# ece411-t4-tx-hand-controlled-robot.net
KiCad netlist of a schematic drawn in EAGLE
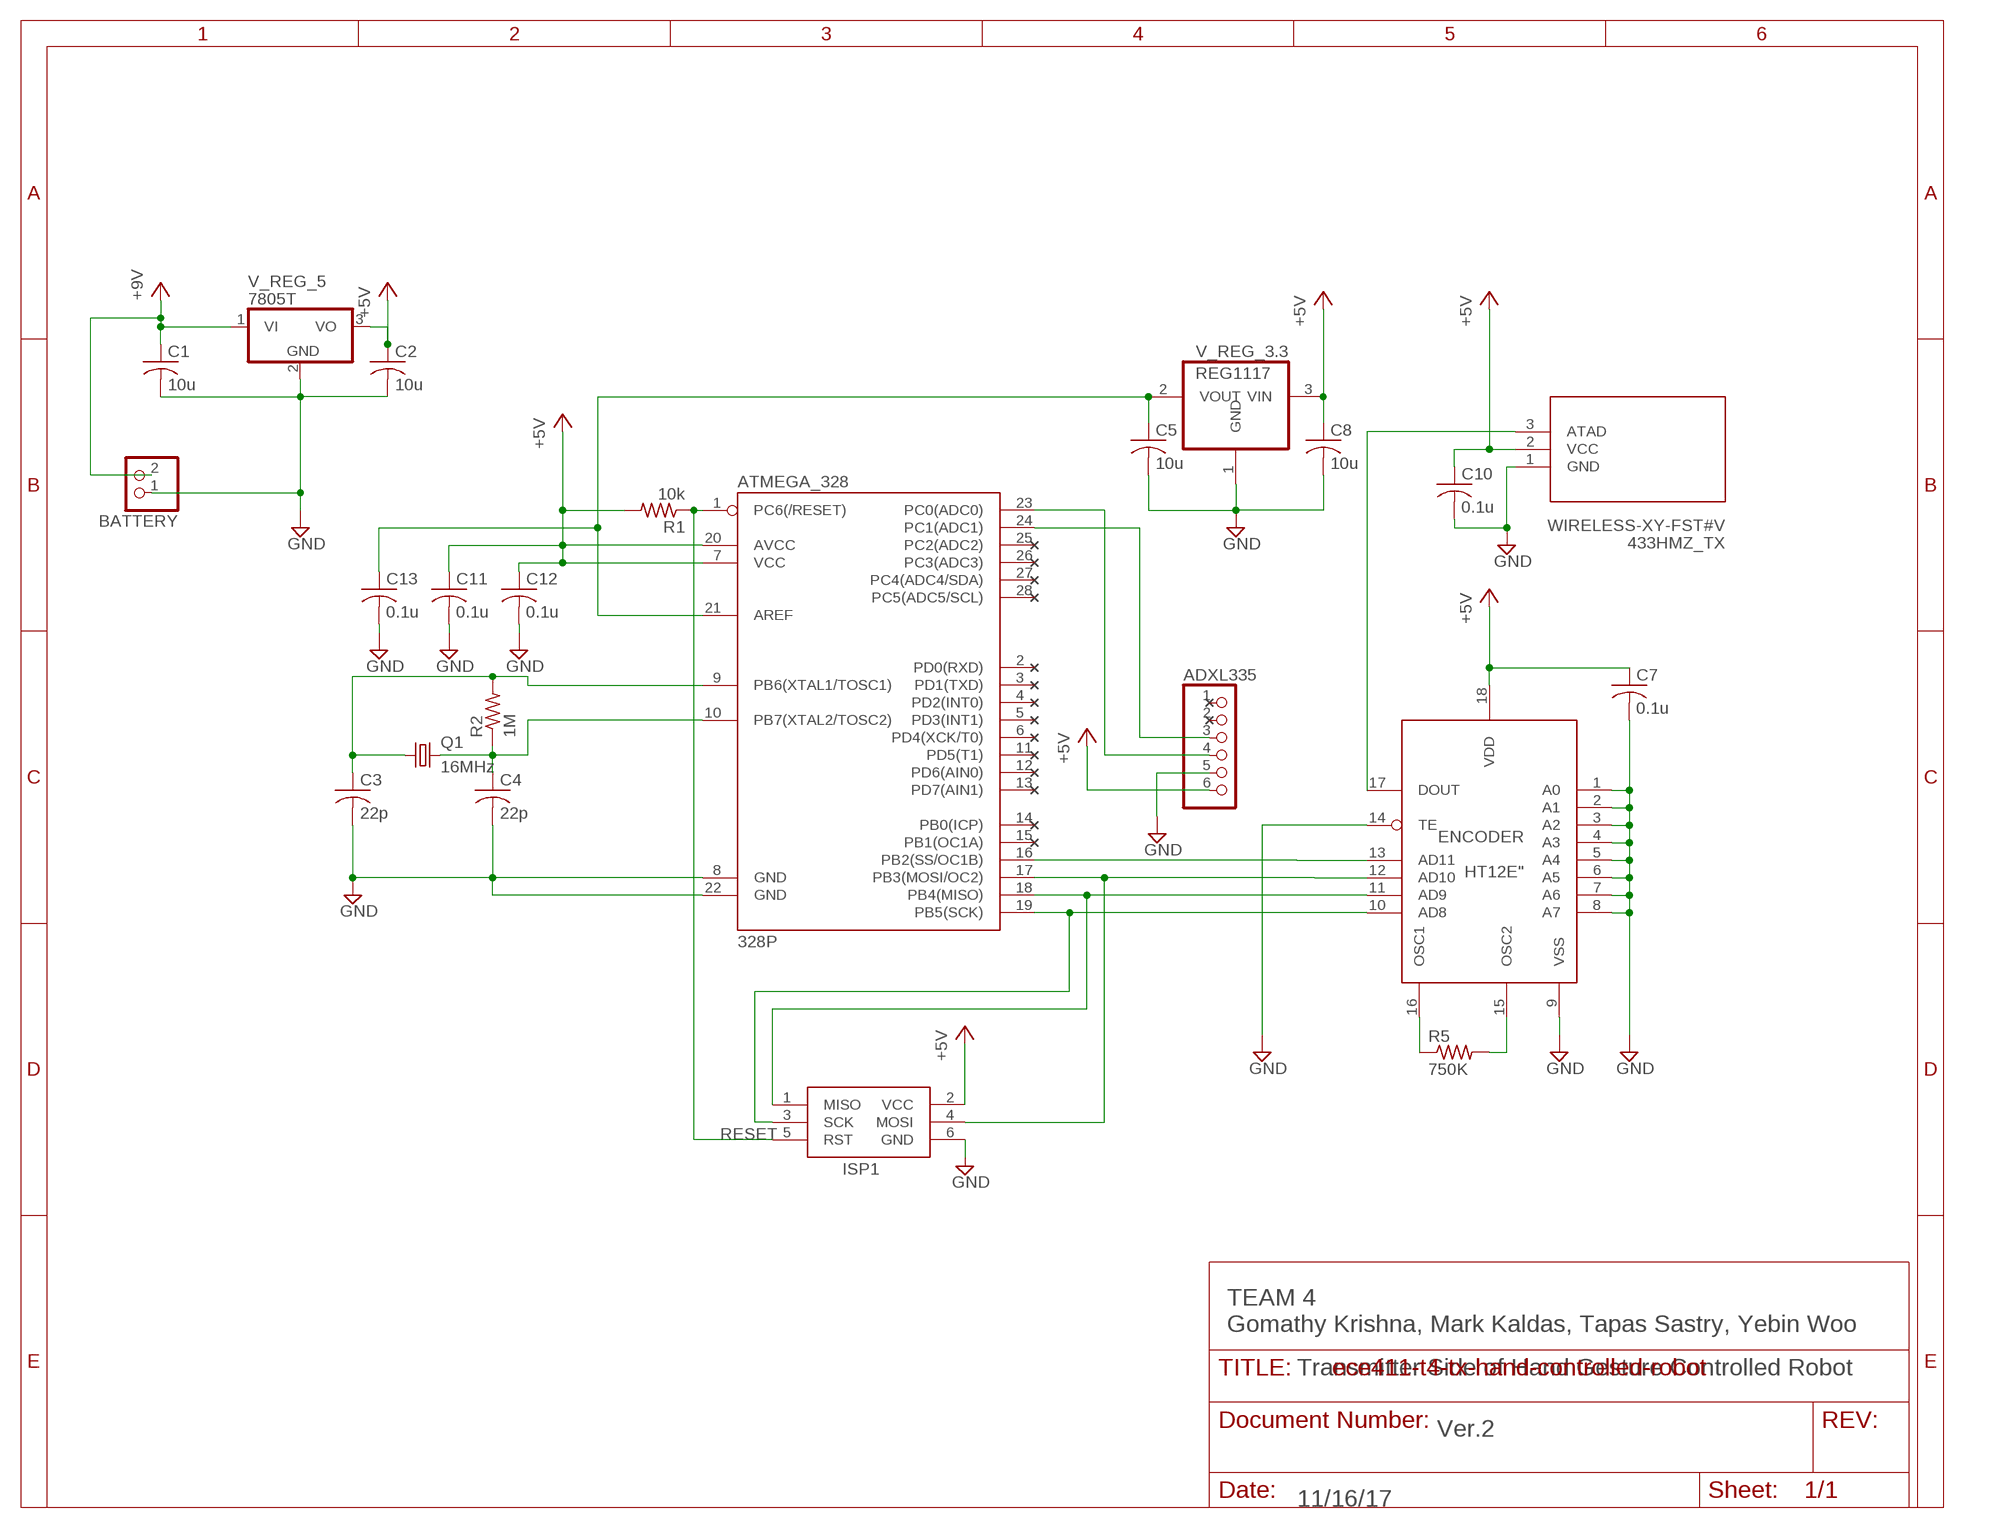
[diagram p0: schematic, sheet 1]

(export (version "E")
  (design (tool "Eeschema 10.0.6"))
  (components
    (comp (ref "433HMZ_TX")
      (value "WIRELESS-XY-FST#V")
      (footprint "eagle-import:WIRELESS-XY-FST#V")
      (libsource (lib "eagle-import") (part "WIRELESS-XY-FST#V"))
    )
    (comp (ref "ADXL335")
      (value "PINHD-1X6")
      (footprint "eagle-import:1X06")
      (libsource (lib "eagle-import") (part "PINHD-1X6"))
    )
    (comp (ref "ATMEGA_328")
      (value "328P")
      (footprint "eagle-import:DIP28")
      (libsource (lib "eagle-import") (part "ATMEGA328P_PDIP"))
    )
    (comp (ref "BATTERY")
      (value "PINHD-1X2")
      (footprint "eagle-import:1X02")
      (libsource (lib "eagle-import") (part "PINHD-1X2"))
    )
    (comp (ref "C1")
      (value "10u")
      (footprint "eagle-import:C0805")
      (libsource (lib "eagle-import") (part "C-USC0805"))
    )
    (comp (ref "C2")
      (value "10u")
      (footprint "eagle-import:C0805")
      (libsource (lib "eagle-import") (part "C-USC0805"))
    )
    (comp (ref "C3")
      (value "22p")
      (footprint "eagle-import:C0805")
      (libsource (lib "eagle-import") (part "C-USC0805"))
    )
    (comp (ref "C4")
      (value "22p")
      (footprint "eagle-import:C0805")
      (libsource (lib "eagle-import") (part "C-USC0805"))
    )
    (comp (ref "C5")
      (value "10u")
      (footprint "eagle-import:C0805")
      (libsource (lib "eagle-import") (part "C-USC0805"))
    )
    (comp (ref "C7")
      (value "0.1u")
      (footprint "eagle-import:C0805")
      (libsource (lib "eagle-import") (part "C-USC0805"))
    )
    (comp (ref "C8")
      (value "10u")
      (footprint "eagle-import:C0805")
      (libsource (lib "eagle-import") (part "C-USC0805"))
    )
    (comp (ref "C10")
      (value "0.1u")
      (footprint "eagle-import:C0805")
      (libsource (lib "eagle-import") (part "C-USC0805"))
    )
    (comp (ref "C11")
      (value "0.1u")
      (footprint "eagle-import:C0805")
      (libsource (lib "eagle-import") (part "C-USC0805"))
    )
    (comp (ref "C12")
      (value "0.1u")
      (footprint "eagle-import:C0805")
      (libsource (lib "eagle-import") (part "C-USC0805"))
    )
    (comp (ref "C13")
      (value "0.1u")
      (footprint "eagle-import:C0805")
      (libsource (lib "eagle-import") (part "C-USC0805"))
    )
    (comp (ref "ENCODER")
      (value "HT12E\"")
      (footprint "eagle-import:18-DIP-A")
      (libsource (lib "eagle-import") (part "HT12E{dblquote}"))
    )
    (comp (ref "ISP1")
      (value "AVRISP-6")
      (footprint "eagle-import:AVRISP")
      (libsource (lib "eagle-import") (part "AVRISP-6"))
    )
    (comp (ref "Q1")
      (value "16MHz")
      (footprint "eagle-import:HC49_S")
      (libsource (lib "eagle-import") (part "CRYTALHC49S"))
    )
    (comp (ref "R1")
      (value "10k")
      (footprint "eagle-import:R0805")
      (libsource (lib "eagle-import") (part "R-US_R0805"))
    )
    (comp (ref "R2")
      (value "1M")
      (footprint "eagle-import:R0805")
      (libsource (lib "eagle-import") (part "R-US_R0805"))
    )
    (comp (ref "R5")
      (value "750K")
      (footprint "eagle-import:R0805")
      (libsource (lib "eagle-import") (part "R-US_R0805"))
    )
    (comp (ref "V_REG_3.3")
      (value "REG1117")
      (footprint "eagle-import:SOT223")
      (libsource (lib "eagle-import") (part "REG1117"))
    )
    (comp (ref "V_REG_5")
      (value "7805T")
      (footprint "eagle-import:TO220H")
      (libsource (lib "eagle-import") (part "78T05"))
    )
  )
  (nets
    (net (code "1") (name "+5V") (class "Default")
      (node (ref "433HMZ_TX") (pin "2") (pinfunction "VCC_2") (pintype "power_in"))
      (node (ref "ADXL335") (pin "6") (pinfunction "6_6") (pintype "passive"))
      (node (ref "ATMEGA_328") (pin "20") (pinfunction "AVCC_20") (pintype "bidirectional"))
      (node (ref "ATMEGA_328") (pin "7") (pinfunction "VCC_7") (pintype "bidirectional"))
      (node (ref "C10") (pin "1") (pinfunction "1_1") (pintype "passive"))
      (node (ref "C11") (pin "1") (pinfunction "1_1") (pintype "passive"))
      (node (ref "C12") (pin "1") (pinfunction "1_1") (pintype "passive"))
      (node (ref "C2") (pin "1") (pinfunction "1_1") (pintype "passive"))
      (node (ref "C7") (pin "1") (pinfunction "1_1") (pintype "passive"))
      (node (ref "C8") (pin "1") (pinfunction "1_1") (pintype "passive"))
      (node (ref "ENCODER") (pin "18") (pinfunction "VDD_18") (pintype "power_in"))
      (node (ref "ISP1") (pin "2") (pinfunction "VCC_2") (pintype "power_in"))
      (node (ref "R1") (pin "2") (pinfunction "2_2") (pintype "passive"))
      (node (ref "V_REG_3.3") (pin "3") (pinfunction "VIN_3") (pintype "input"))
      (node (ref "V_REG_5") (pin "3") (pinfunction "VO_3") (pintype "passive"))
    )
    (net (code "2") (name "+9V") (class "Default")
      (node (ref "BATTERY") (pin "2") (pinfunction "2_2") (pintype "passive"))
      (node (ref "C1") (pin "1") (pinfunction "1_1") (pintype "passive"))
      (node (ref "V_REG_5") (pin "1") (pinfunction "VI_1") (pintype "input"))
    )
    (net (code "3") (name "/RESET") (class "Default")
      (node (ref "ATMEGA_328") (pin "1") (pinfunction "PC6(/RESET)_1") (pintype "bidirectional"))
      (node (ref "ISP1") (pin "5") (pinfunction "RST_5") (pintype "output"))
      (node (ref "R1") (pin "1") (pinfunction "1_1") (pintype "passive"))
    )
    (net (code "4") (name "GND") (class "Default")
      (node (ref "433HMZ_TX") (pin "1") (pinfunction "GND_1") (pintype "power_in"))
      (node (ref "ADXL335") (pin "5") (pinfunction "5_5") (pintype "passive"))
      (node (ref "ATMEGA_328") (pin "22") (pinfunction "GND_22") (pintype "bidirectional"))
      (node (ref "ATMEGA_328") (pin "8") (pinfunction "GND_8") (pintype "bidirectional"))
      (node (ref "BATTERY") (pin "1") (pinfunction "1_1") (pintype "passive"))
      (node (ref "C1") (pin "2") (pinfunction "2_2") (pintype "passive"))
      (node (ref "C10") (pin "2") (pinfunction "2_2") (pintype "passive"))
      (node (ref "C11") (pin "2") (pinfunction "2_2") (pintype "passive"))
      (node (ref "C12") (pin "2") (pinfunction "2_2") (pintype "passive"))
      (node (ref "C13") (pin "2") (pinfunction "2_2") (pintype "passive"))
      (node (ref "C2") (pin "2") (pinfunction "2_2") (pintype "passive"))
      (node (ref "C3") (pin "2") (pinfunction "2_2") (pintype "passive"))
      (node (ref "C4") (pin "2") (pinfunction "2_2") (pintype "passive"))
      (node (ref "C5") (pin "2") (pinfunction "2_2") (pintype "passive"))
      (node (ref "C7") (pin "2") (pinfunction "2_2") (pintype "passive"))
      (node (ref "C8") (pin "2") (pinfunction "2_2") (pintype "passive"))
      (node (ref "ENCODER") (pin "1") (pinfunction "A0_1") (pintype "input"))
      (node (ref "ENCODER") (pin "14") (pinfunction "TE_14") (pintype "power_in"))
      (node (ref "ENCODER") (pin "2") (pinfunction "A1_2") (pintype "input"))
      (node (ref "ENCODER") (pin "3") (pinfunction "A2_3") (pintype "input"))
      (node (ref "ENCODER") (pin "4") (pinfunction "A3_4") (pintype "input"))
      (node (ref "ENCODER") (pin "5") (pinfunction "A4_5") (pintype "input"))
      (node (ref "ENCODER") (pin "6") (pinfunction "A5_6") (pintype "input"))
      (node (ref "ENCODER") (pin "7") (pinfunction "A6_7") (pintype "input"))
      (node (ref "ENCODER") (pin "8") (pinfunction "A7_8") (pintype "input"))
      (node (ref "ENCODER") (pin "9") (pinfunction "VSS_9") (pintype "power_in"))
      (node (ref "ISP1") (pin "6") (pinfunction "GND_6") (pintype "power_in"))
      (node (ref "V_REG_3.3") (pin "1") (pinfunction "GND_1") (pintype "power_in"))
      (node (ref "V_REG_5") (pin "2") (pinfunction "GND_2") (pintype "passive"))
    )
    (net (code "5") (name "Net-(433HMZ_TX-ATAD)") (class "Default")
      (node (ref "433HMZ_TX") (pin "3") (pinfunction "ATAD_3") (pintype "input"))
      (node (ref "ENCODER") (pin "17") (pinfunction "DOUT_17") (pintype "output"))
    )
    (net (code "6") (name "Net-(ATMEGA_328-AREF)") (class "Default")
      (node (ref "ATMEGA_328") (pin "21") (pinfunction "AREF_21") (pintype "bidirectional"))
      (node (ref "C13") (pin "1") (pinfunction "1_1") (pintype "passive"))
      (node (ref "C5") (pin "1") (pinfunction "1_1") (pintype "passive"))
      (node (ref "V_REG_3.3") (pin "2") (pinfunction "VOUT_2") (pintype "output"))
    )
    (net (code "7") (name "Net-(ATMEGA_328-PB2(SS{slash}OC1B))") (class "Default")
      (node (ref "ATMEGA_328") (pin "16") (pinfunction "PB2(SS/OC1B)_16") (pintype "bidirectional"))
      (node (ref "ENCODER") (pin "13") (pinfunction "AD11_13") (pintype "input"))
    )
    (net (code "8") (name "Net-(ATMEGA_328-PB3(MOSI{slash}OC2))") (class "Default")
      (node (ref "ATMEGA_328") (pin "17") (pinfunction "PB3(MOSI/OC2)_17") (pintype "bidirectional"))
      (node (ref "ENCODER") (pin "12") (pinfunction "AD10_12") (pintype "input"))
      (node (ref "ISP1") (pin "4") (pinfunction "MOSI_4") (pintype "output"))
    )
    (net (code "9") (name "Net-(ATMEGA_328-PB4(MISO))") (class "Default")
      (node (ref "ATMEGA_328") (pin "18") (pinfunction "PB4(MISO)_18") (pintype "bidirectional"))
      (node (ref "ENCODER") (pin "11") (pinfunction "AD9_11") (pintype "input"))
      (node (ref "ISP1") (pin "1") (pinfunction "MISO_1") (pintype "input"))
    )
    (net (code "10") (name "Net-(ATMEGA_328-PB5(SCK))") (class "Default")
      (node (ref "ATMEGA_328") (pin "19") (pinfunction "PB5(SCK)_19") (pintype "bidirectional"))
      (node (ref "ENCODER") (pin "10") (pinfunction "AD8_10") (pintype "input"))
      (node (ref "ISP1") (pin "3") (pinfunction "SCK_3") (pintype "output"))
    )
    (net (code "11") (name "Net-(ATMEGA_328-PB6(XTAL1{slash}TOSC1))") (class "Default")
      (node (ref "ATMEGA_328") (pin "9") (pinfunction "PB6(XTAL1/TOSC1)_9") (pintype "bidirectional"))
      (node (ref "C3") (pin "1") (pinfunction "1_1") (pintype "passive"))
      (node (ref "Q1") (pin "1") (pinfunction "1_1") (pintype "passive"))
      (node (ref "R2") (pin "2") (pinfunction "2_2") (pintype "passive"))
    )
    (net (code "12") (name "Net-(ATMEGA_328-PB7(XTAL2{slash}TOSC2))") (class "Default")
      (node (ref "ATMEGA_328") (pin "10") (pinfunction "PB7(XTAL2/TOSC2)_10") (pintype "bidirectional"))
      (node (ref "C4") (pin "1") (pinfunction "1_1") (pintype "passive"))
      (node (ref "Q1") (pin "2") (pinfunction "2_2") (pintype "passive"))
      (node (ref "R2") (pin "1") (pinfunction "1_1") (pintype "passive"))
    )
    (net (code "13") (name "Net-(ATMEGA_328-PC0(ADC0))") (class "Default")
      (node (ref "ADXL335") (pin "4") (pinfunction "4_4") (pintype "passive"))
      (node (ref "ATMEGA_328") (pin "23") (pinfunction "PC0(ADC0)_23") (pintype "bidirectional"))
    )
    (net (code "14") (name "Net-(ATMEGA_328-PC1(ADC1))") (class "Default")
      (node (ref "ADXL335") (pin "3") (pinfunction "3_3") (pintype "passive"))
      (node (ref "ATMEGA_328") (pin "24") (pinfunction "PC1(ADC1)_24") (pintype "bidirectional"))
    )
    (net (code "15") (name "Net-(ENCODER-OSC1)") (class "Default")
      (node (ref "ENCODER") (pin "16") (pinfunction "OSC1_16") (pintype "input"))
      (node (ref "R5") (pin "1") (pinfunction "1_1") (pintype "passive"))
    )
    (net (code "16") (name "Net-(ENCODER-OSC2)") (class "Default")
      (node (ref "ENCODER") (pin "15") (pinfunction "OSC2_15") (pintype "input"))
      (node (ref "R5") (pin "2") (pinfunction "2_2") (pintype "passive"))
    )
    (net (code "17") (name "unconnected-(ADXL335-Pad1)") (class "Default")
      (node (ref "ADXL335") (pin "1") (pinfunction "1_1") (pintype "passive"))
    )
    (net (code "18") (name "unconnected-(ADXL335-Pad2)") (class "Default")
      (node (ref "ADXL335") (pin "2") (pinfunction "2_2") (pintype "passive"))
    )
    (net (code "19") (name "unconnected-(ATMEGA_328-PB0(ICP)-Pad14)") (class "Default")
      (node (ref "ATMEGA_328") (pin "14") (pinfunction "PB0(ICP)_14") (pintype "bidirectional"))
    )
    (net (code "20") (name "unconnected-(ATMEGA_328-PB1(OC1A)-Pad15)") (class "Default")
      (node (ref "ATMEGA_328") (pin "15") (pinfunction "PB1(OC1A)_15") (pintype "bidirectional"))
    )
    (net (code "21") (name "unconnected-(ATMEGA_328-PC2(ADC2)-Pad25)") (class "Default")
      (node (ref "ATMEGA_328") (pin "25") (pinfunction "PC2(ADC2)_25") (pintype "bidirectional"))
    )
    (net (code "22") (name "unconnected-(ATMEGA_328-PC3(ADC3)-Pad26)") (class "Default")
      (node (ref "ATMEGA_328") (pin "26") (pinfunction "PC3(ADC3)_26") (pintype "bidirectional"))
    )
    (net (code "23") (name "unconnected-(ATMEGA_328-PC4(ADC4{slash}SDA)-Pad27)") (class "Default")
      (node (ref "ATMEGA_328") (pin "27") (pinfunction "PC4(ADC4/SDA)_27") (pintype "bidirectional"))
    )
    (net (code "24") (name "unconnected-(ATMEGA_328-PC5(ADC5{slash}SCL)-Pad28)") (class "Default")
      (node (ref "ATMEGA_328") (pin "28") (pinfunction "PC5(ADC5/SCL)_28") (pintype "bidirectional"))
    )
    (net (code "25") (name "unconnected-(ATMEGA_328-PD0(RXD)-Pad2)") (class "Default")
      (node (ref "ATMEGA_328") (pin "2") (pinfunction "PD0(RXD)_2") (pintype "bidirectional"))
    )
    (net (code "26") (name "unconnected-(ATMEGA_328-PD1(TXD)-Pad3)") (class "Default")
      (node (ref "ATMEGA_328") (pin "3") (pinfunction "PD1(TXD)_3") (pintype "bidirectional"))
    )
    (net (code "27") (name "unconnected-(ATMEGA_328-PD2(INT0)-Pad4)") (class "Default")
      (node (ref "ATMEGA_328") (pin "4") (pinfunction "PD2(INT0)_4") (pintype "bidirectional"))
    )
    (net (code "28") (name "unconnected-(ATMEGA_328-PD3(INT1)-Pad5)") (class "Default")
      (node (ref "ATMEGA_328") (pin "5") (pinfunction "PD3(INT1)_5") (pintype "bidirectional"))
    )
    (net (code "29") (name "unconnected-(ATMEGA_328-PD4(XCK{slash}T0)-Pad6)") (class "Default")
      (node (ref "ATMEGA_328") (pin "6") (pinfunction "PD4(XCK/T0)_6") (pintype "bidirectional"))
    )
    (net (code "30") (name "unconnected-(ATMEGA_328-PD5(T1)-Pad11)") (class "Default")
      (node (ref "ATMEGA_328") (pin "11") (pinfunction "PD5(T1)_11") (pintype "bidirectional"))
    )
    (net (code "31") (name "unconnected-(ATMEGA_328-PD6(AIN0)-Pad12)") (class "Default")
      (node (ref "ATMEGA_328") (pin "12") (pinfunction "PD6(AIN0)_12") (pintype "bidirectional"))
    )
    (net (code "32") (name "unconnected-(ATMEGA_328-PD7(AIN1)-Pad13)") (class "Default")
      (node (ref "ATMEGA_328") (pin "13") (pinfunction "PD7(AIN1)_13") (pintype "bidirectional"))
    )
  )
)
